# Fri3d_2026_DJ_00.net
KiCad netlist of a schematic drawn in Altium Designer
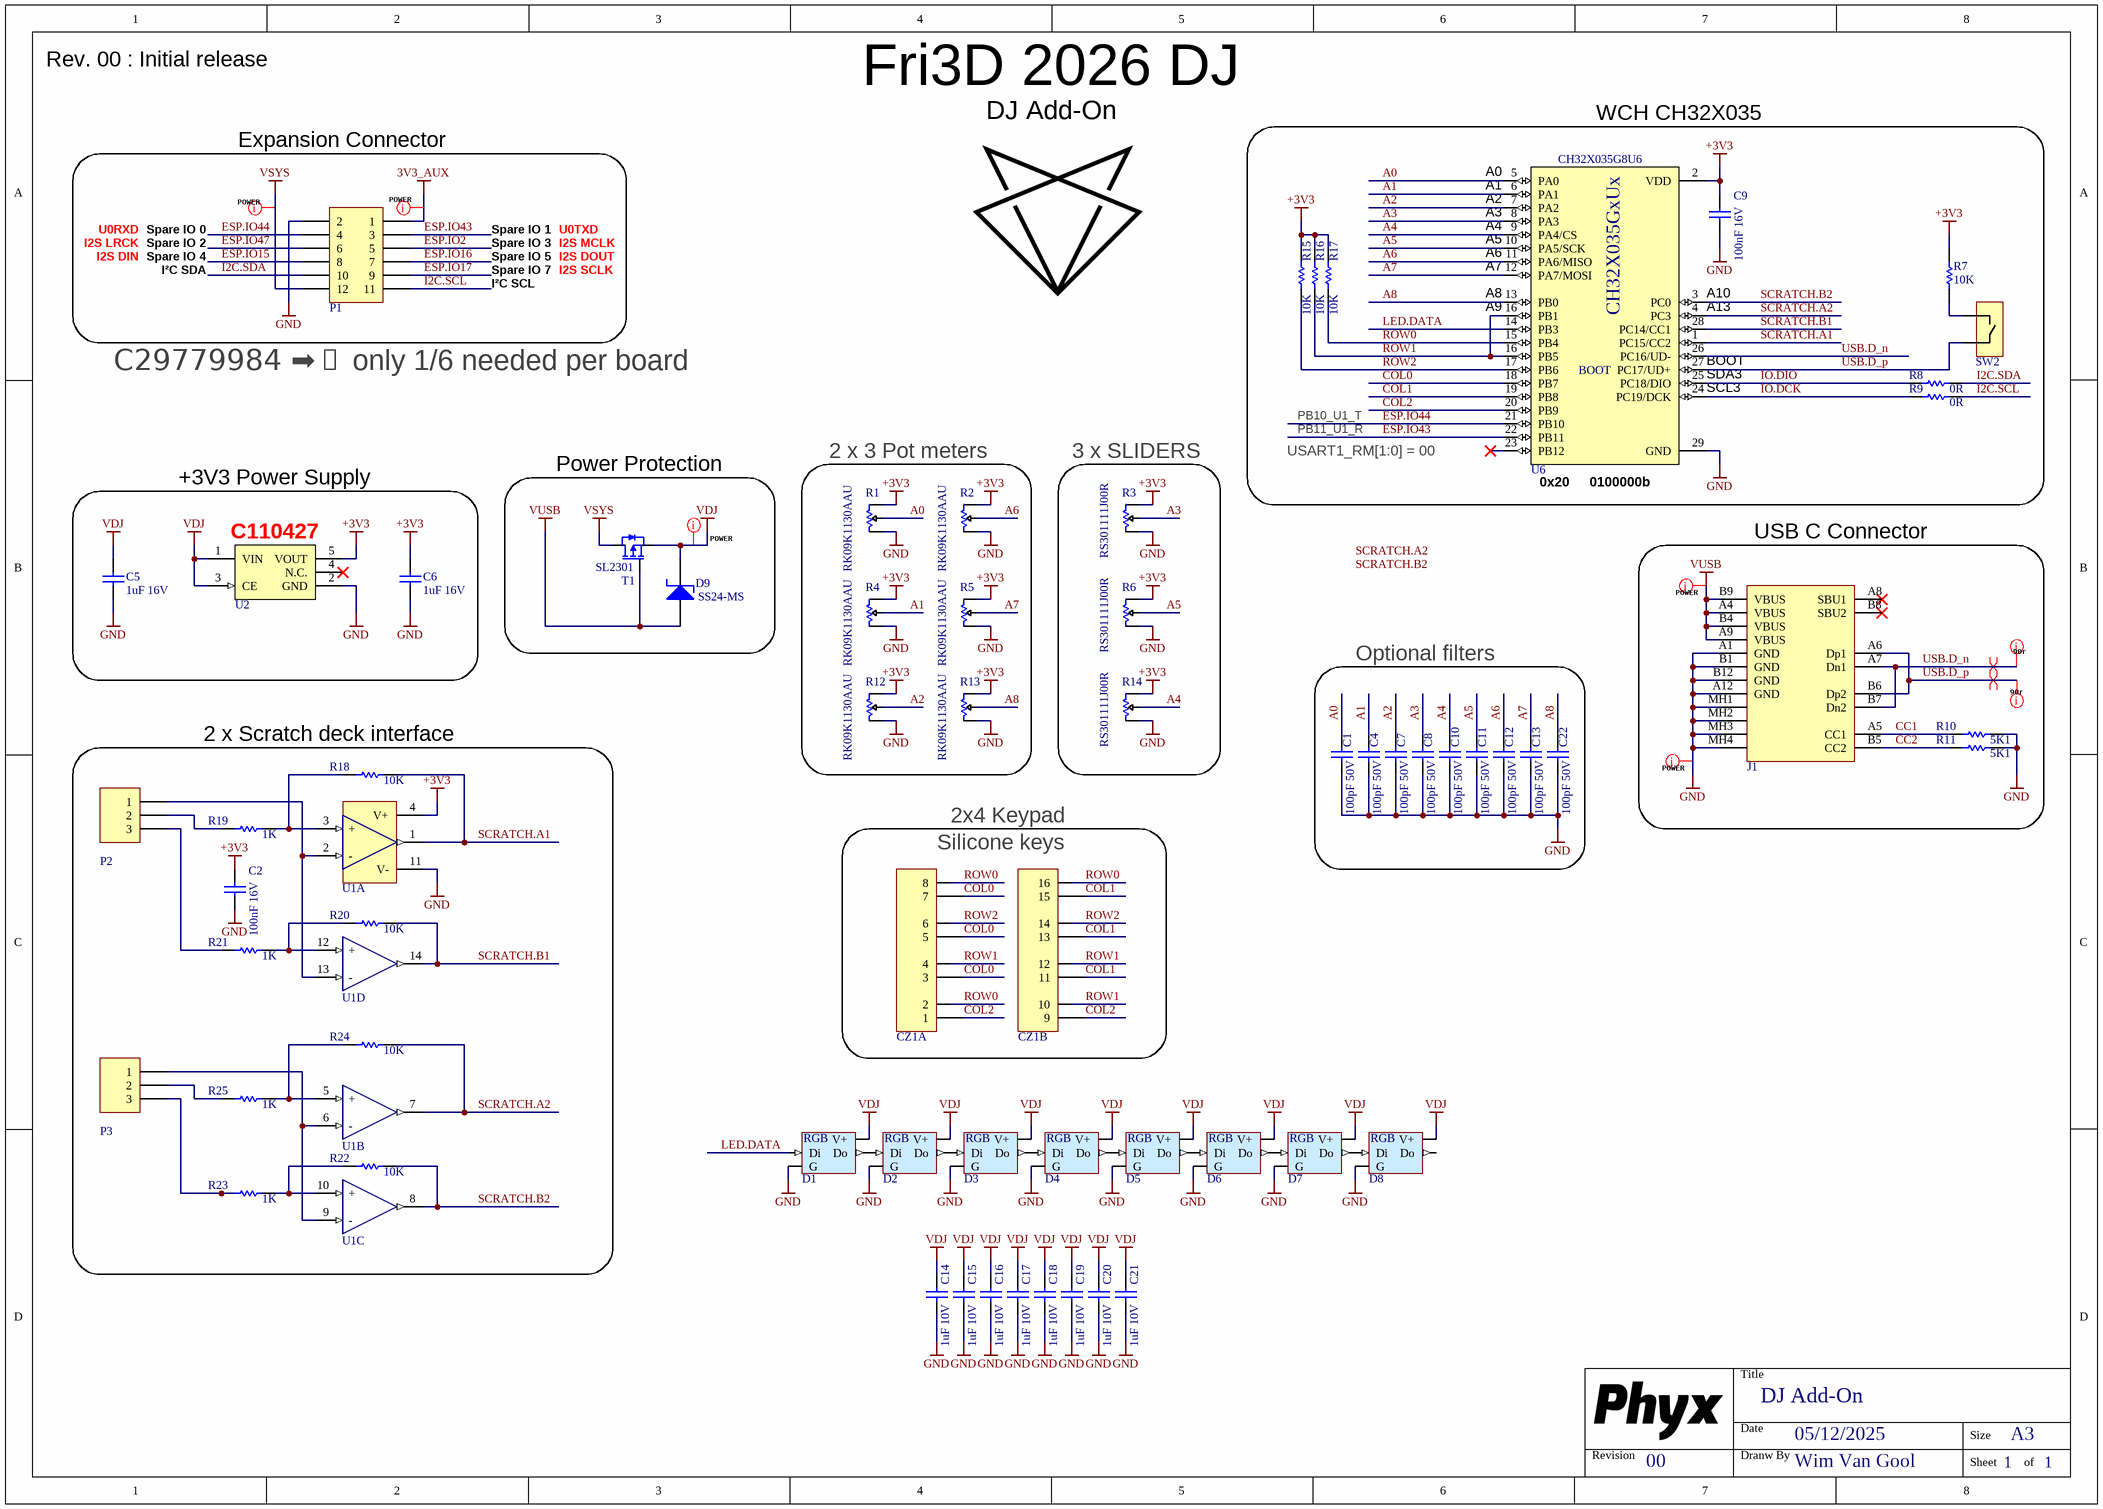
[diagram p0: Fri3d_2026_DJ_00.SchDoc]

(export (version "E")
  (design (tool "Eeschema 10.0.6"))
  (components
    (comp (ref "C1")
      (value "100pF 50V")
      (footprint "C0603_N")
      (description "Capacitor Ceramic")
      (libsource (lib "Phyx_Components") (part "CAP_CERAMIC"))
    )
    (comp (ref "C2")
      (value "100nF 16V")
      (footprint "C0603_N")
      (description "Capacitor Ceramic")
      (libsource (lib "Phyx_Components") (part "CAP_CERAMIC"))
    )
    (comp (ref "C4")
      (value "100pF 50V")
      (footprint "C0603_N")
      (description "Capacitor Ceramic")
      (libsource (lib "Phyx_Components") (part "CAP_CERAMIC"))
    )
    (comp (ref "C5")
      (value "1uF 16V")
      (footprint "C0603_N")
      (description "Capacitor Ceramic")
      (libsource (lib "Phyx_Components") (part "CAP_CERAMIC"))
    )
    (comp (ref "C6")
      (value "1uF 16V")
      (footprint "C0603_N")
      (description "Capacitor Ceramic")
      (libsource (lib "Phyx_Components") (part "CAP_CERAMIC"))
    )
    (comp (ref "C7")
      (value "100pF 50V")
      (footprint "C0603_N")
      (description "Capacitor Ceramic")
      (libsource (lib "Phyx_Components") (part "CAP_CERAMIC"))
    )
    (comp (ref "C8")
      (value "100pF 50V")
      (footprint "C0603_N")
      (description "Capacitor Ceramic")
      (libsource (lib "Phyx_Components") (part "CAP_CERAMIC"))
    )
    (comp (ref "C9")
      (value "100nF 16V")
      (footprint "C0603_N")
      (description "Capacitor Ceramic")
      (libsource (lib "Phyx_Components") (part "CAP_CERAMIC"))
    )
    (comp (ref "C10")
      (value "100pF 50V")
      (footprint "C0603_N")
      (description "Capacitor Ceramic")
      (libsource (lib "Phyx_Components") (part "CAP_CERAMIC"))
    )
    (comp (ref "C11")
      (value "100pF 50V")
      (footprint "C0603_N")
      (description "Capacitor Ceramic")
      (libsource (lib "Phyx_Components") (part "CAP_CERAMIC"))
    )
    (comp (ref "C12")
      (value "100pF 50V")
      (footprint "C0603_N")
      (description "Capacitor Ceramic")
      (libsource (lib "Phyx_Components") (part "CAP_CERAMIC"))
    )
    (comp (ref "C13")
      (value "100pF 50V")
      (footprint "C0603_N")
      (description "Capacitor Ceramic")
      (libsource (lib "Phyx_Components") (part "CAP_CERAMIC"))
    )
    (comp (ref "C14")
      (value "1uF 10V")
      (footprint "C0402")
      (description "Capacitor Ceramic")
      (libsource (lib "Phyx_Components") (part "CAP_CERAMIC"))
    )
    (comp (ref "C15")
      (value "1uF 10V")
      (footprint "C0402")
      (description "Capacitor Ceramic")
      (libsource (lib "Phyx_Components") (part "CAP_CERAMIC"))
    )
    (comp (ref "C16")
      (value "1uF 10V")
      (footprint "C0402")
      (description "Capacitor Ceramic")
      (libsource (lib "Phyx_Components") (part "CAP_CERAMIC"))
    )
    (comp (ref "C17")
      (value "1uF 10V")
      (footprint "C0402")
      (description "Capacitor Ceramic")
      (libsource (lib "Phyx_Components") (part "CAP_CERAMIC"))
    )
    (comp (ref "C18")
      (value "1uF 10V")
      (footprint "C0402")
      (description "Capacitor Ceramic")
      (libsource (lib "Phyx_Components") (part "CAP_CERAMIC"))
    )
    (comp (ref "C19")
      (value "1uF 10V")
      (footprint "C0402")
      (description "Capacitor Ceramic")
      (libsource (lib "Phyx_Components") (part "CAP_CERAMIC"))
    )
    (comp (ref "C20")
      (value "1uF 10V")
      (footprint "C0402")
      (description "Capacitor Ceramic")
      (libsource (lib "Phyx_Components") (part "CAP_CERAMIC"))
    )
    (comp (ref "C21")
      (value "1uF 10V")
      (footprint "C0402")
      (description "Capacitor Ceramic")
      (libsource (lib "Phyx_Components") (part "CAP_CERAMIC"))
    )
    (comp (ref "C22")
      (value "100pF 50V")
      (footprint "C0603_N")
      (description "Capacitor Ceramic")
      (libsource (lib "Phyx_Components") (part "CAP_CERAMIC"))
    )
    (comp (ref "CZ1")
      (value "Campzone 2020 2x4 silicone keypad")
      (footprint "CZ20_2x4")
      (libsource (lib "Phyx_Components") (part "CZ20_2x4"))
    )
    (comp (ref "D1")
      (value "WS2812 based digital RGB LED 5050 White package reduced current")
      (footprint "LED_5050_WS2812B_WHITE")
      (description "=Description")
      (libsource (lib "Phyx_Components") (part "LED_RGB_WS2812B_5050"))
    )
    (comp (ref "D2")
      (value "WS2812 based digital RGB LED 5050 White package reduced current")
      (footprint "LED_5050_WS2812B_WHITE")
      (description "=Description")
      (libsource (lib "Phyx_Components") (part "LED_RGB_WS2812B_5050"))
    )
    (comp (ref "D3")
      (value "WS2812 based digital RGB LED 5050 White package reduced current")
      (footprint "LED_5050_WS2812B_WHITE")
      (description "=Description")
      (libsource (lib "Phyx_Components") (part "LED_RGB_WS2812B_5050"))
    )
    (comp (ref "D4")
      (value "WS2812 based digital RGB LED 5050 White package reduced current")
      (footprint "LED_5050_WS2812B_WHITE")
      (description "=Description")
      (libsource (lib "Phyx_Components") (part "LED_RGB_WS2812B_5050"))
    )
    (comp (ref "D5")
      (value "WS2812 based digital RGB LED 5050 White package reduced current")
      (footprint "LED_5050_WS2812B_WHITE")
      (description "=Description")
      (libsource (lib "Phyx_Components") (part "LED_RGB_WS2812B_5050"))
    )
    (comp (ref "D6")
      (value "WS2812 based digital RGB LED 5050 White package reduced current")
      (footprint "LED_5050_WS2812B_WHITE")
      (description "=Description")
      (libsource (lib "Phyx_Components") (part "LED_RGB_WS2812B_5050"))
    )
    (comp (ref "D7")
      (value "WS2812 based digital RGB LED 5050 White package reduced current")
      (footprint "LED_5050_WS2812B_WHITE")
      (description "=Description")
      (libsource (lib "Phyx_Components") (part "LED_RGB_WS2812B_5050"))
    )
    (comp (ref "D8")
      (value "WS2812 based digital RGB LED 5050 White package reduced current")
      (footprint "LED_5050_WS2812B_WHITE")
      (description "=Description")
      (libsource (lib "Phyx_Components") (part "LED_RGB_WS2812B_5050"))
    )
    (comp (ref "D9")
      (value "SS24-MS")
      (footprint "DO-214AC_AC")
      (description "=Description")
      (fields (field (name "Comment") "40V 2A 550mV@2A DO-214 Schottky"))
      (libsource (lib "Phyx_Components") (part "Schottky_AC"))
    )
    (comp (ref "J1")
      (value "USB 2.0 C Reversible Receptacle Horizontal full SMD")
      (footprint "XUNPU-TYPEC-304S-ACP16")
      (libsource (lib "Phyx_Components") (part "USB_C_16_4"))
    )
    (comp (ref "P1")
      (value "Header 6X2")
      (footprint "HDR2X6")
      (libsource (lib "Phyx_Components") (part "Header 6X2"))
    )
    (comp (ref "P2")
      (value "Header 3")
      (footprint "HDR1X3")
      (description "Pin Header 2.54mm 3way")
      (libsource (lib "Phyx_Components") (part "Header 3"))
    )
    (comp (ref "P3")
      (value "Header 3")
      (footprint "HDR1X3")
      (description "Pin Header 2.54mm 3way")
      (libsource (lib "Phyx_Components") (part "Header 3"))
    )
    (comp (ref "R1")
      (value "RK09K1130AAU")
      (footprint "ALPS_RK09K1130AAU")
      (fields (field (name "Comment") "10kΩ Rotary Potentiometers"))
      (libsource (lib "Phyx_Components") (part "RES_VAR"))
    )
    (comp (ref "R2")
      (value "RK09K1130AAU")
      (footprint "ALPS_RK09K1130AAU")
      (fields (field (name "Comment") "10kΩ Rotary Potentiometers"))
      (libsource (lib "Phyx_Components") (part "RES_VAR"))
    )
    (comp (ref "R3")
      (value "RS301111J00R")
      (footprint "ALPS_RS301111J00R")
      (fields (field (name "Comment") "50kΩ Slide Potentiometers"))
      (libsource (lib "Phyx_Components") (part "RES_VAR"))
    )
    (comp (ref "R4")
      (value "RK09K1130AAU")
      (footprint "ALPS_RK09K1130AAU")
      (fields (field (name "Comment") "10kΩ Rotary Potentiometers"))
      (libsource (lib "Phyx_Components") (part "RES_VAR"))
    )
    (comp (ref "R5")
      (value "RK09K1130AAU")
      (footprint "ALPS_RK09K1130AAU")
      (fields (field (name "Comment") "10kΩ Rotary Potentiometers"))
      (libsource (lib "Phyx_Components") (part "RES_VAR"))
    )
    (comp (ref "R6")
      (value "RS301111J00R")
      (footprint "ALPS_RS301111J00R")
      (fields (field (name "Comment") "50kΩ Slide Potentiometers"))
      (libsource (lib "Phyx_Components") (part "RES_VAR"))
    )
    (comp (ref "R7")
      (value "10K")
      (footprint "R0603_N")
      (libsource (lib "Phyx_Components") (part "RESISTOR"))
    )
    (comp (ref "R8") (value "0R") (footprint "R0603_N") (libsource (lib "Phyx_Components") (part "RESISTOR")))
    (comp (ref "R9") (value "0R") (footprint "R0603_N") (libsource (lib "Phyx_Components") (part "RESISTOR")))
    (comp (ref "R10")
      (value "5K1")
      (footprint "R0603_N")
      (libsource (lib "Phyx_Components") (part "RESISTOR"))
    )
    (comp (ref "R11")
      (value "5K1")
      (footprint "R0603_N")
      (libsource (lib "Phyx_Components") (part "RESISTOR"))
    )
    (comp (ref "R12")
      (value "RK09K1130AAU")
      (footprint "ALPS_RK09K1130AAU")
      (fields (field (name "Comment") "10kΩ Rotary Potentiometers"))
      (libsource (lib "Phyx_Components") (part "RES_VAR"))
    )
    (comp (ref "R13")
      (value "RK09K1130AAU")
      (footprint "ALPS_RK09K1130AAU")
      (fields (field (name "Comment") "10kΩ Rotary Potentiometers"))
      (libsource (lib "Phyx_Components") (part "RES_VAR"))
    )
    (comp (ref "R14")
      (value "RS301111J00R")
      (footprint "ALPS_RS301111J00R")
      (fields (field (name "Comment") "50kΩ Slide Potentiometers"))
      (libsource (lib "Phyx_Components") (part "RES_VAR"))
    )
    (comp (ref "R15")
      (value "10K")
      (footprint "R0603_N")
      (libsource (lib "Phyx_Components") (part "RESISTOR"))
    )
    (comp (ref "R16")
      (value "10K")
      (footprint "R0603_N")
      (libsource (lib "Phyx_Components") (part "RESISTOR"))
    )
    (comp (ref "R17")
      (value "10K")
      (footprint "R0603_N")
      (libsource (lib "Phyx_Components") (part "RESISTOR"))
    )
    (comp (ref "R18")
      (value "10K")
      (footprint "R0603_N")
      (libsource (lib "Phyx_Components") (part "RESISTOR"))
    )
    (comp (ref "R19")
      (value "1K")
      (footprint "R0603_N")
      (libsource (lib "Phyx_Components") (part "RESISTOR"))
    )
    (comp (ref "R20")
      (value "10K")
      (footprint "R0603_N")
      (libsource (lib "Phyx_Components") (part "RESISTOR"))
    )
    (comp (ref "R21")
      (value "1K")
      (footprint "R0603_N")
      (libsource (lib "Phyx_Components") (part "RESISTOR"))
    )
    (comp (ref "R22")
      (value "10K")
      (footprint "R0603_N")
      (libsource (lib "Phyx_Components") (part "RESISTOR"))
    )
    (comp (ref "R23")
      (value "1K")
      (footprint "R0603_N")
      (libsource (lib "Phyx_Components") (part "RESISTOR"))
    )
    (comp (ref "R24")
      (value "10K")
      (footprint "R0603_N")
      (libsource (lib "Phyx_Components") (part "RESISTOR"))
    )
    (comp (ref "R25")
      (value "1K")
      (footprint "R0603_N")
      (libsource (lib "Phyx_Components") (part "RESISTOR"))
    )
    (comp (ref "SW2")
      (value "4.5x4.5mm tact SMD H3,8mm")
      (footprint "WE_430181038816")
      (libsource (lib "Phyx_Components") (part "SW_TACT"))
    )
    (comp (ref "T1")
      (value "SL2301")
      (footprint "SOT23-3")
      (description "=Description")
      (fields (field (name "Comment") "-2.3A -20V P-Ch MOSFET Vgs -1V"))
      (libsource (lib "Phyx_Components") (part "P_MOSFET_GSD"))
    )
    (comp (ref "U1")
      (value "Quad, 30-V, 1-MHz operational amplifier")
      (footprint "SOIC_N_14")
      (description "=Description")
      (libsource (lib "Phyx_Components") (part "OPA4134"))
    )
    (comp (ref "U2")
      (value "3V3 LDO 300mA 150mV")
      (footprint "SOT23-5")
      (description "=Designator")
      (libsource (lib "Phyx_Components") (part "XC6210_SOT"))
    )
    (comp (ref "U6")
      (value "CH32X035G8U6")
      (footprint "QFN_28_4.0x4.0_P0.4")
      (fields
        (field (name "Comment") "WCH CH32X035G8U6 QFN28 RISC-V 32-bit MCU, 62KB Flash, 10KB RAM, USB PD")
      )
      (libsource (lib "Phyx_Components") (part "WCH_CH32X035GxUx"))
    )
  )
  (nets
    (net (code "1") (name "+3V3") (class "Default")
      (node (ref "C2") (pin "1") (pinfunction "1_1") (pintype "passive"))
      (node (ref "C6") (pin "1") (pinfunction "1_1") (pintype "passive"))
      (node (ref "C9") (pin "1") (pinfunction "1_1") (pintype "passive"))
      (node (ref "R1") (pin "1") (pinfunction "1_1") (pintype "passive"))
      (node (ref "R12") (pin "1") (pinfunction "1_1") (pintype "passive"))
      (node (ref "R13") (pin "1") (pinfunction "1_1") (pintype "passive"))
      (node (ref "R14") (pin "1") (pinfunction "1_1") (pintype "passive"))
      (node (ref "R15") (pin "1") (pinfunction "1_1") (pintype "passive"))
      (node (ref "R16") (pin "1") (pinfunction "1_1") (pintype "passive"))
      (node (ref "R17") (pin "1") (pinfunction "1_1") (pintype "passive"))
      (node (ref "R2") (pin "1") (pinfunction "1_1") (pintype "passive"))
      (node (ref "R3") (pin "1") (pinfunction "1_1") (pintype "passive"))
      (node (ref "R4") (pin "1") (pinfunction "1_1") (pintype "passive"))
      (node (ref "R5") (pin "1") (pinfunction "1_1") (pintype "passive"))
      (node (ref "R6") (pin "1") (pinfunction "1_1") (pintype "passive"))
      (node (ref "R7") (pin "1") (pinfunction "1_1") (pintype "passive"))
      (node (ref "U1") (pin "4") (pinfunction "V+_4") (pintype "power_in"))
      (node (ref "U2") (pin "5") (pinfunction "VOUT_5") (pintype "power_in"))
      (node (ref "U6") (pin "2") (pinfunction "VDD_2") (pintype "power_in"))
    )
    (net (code "2") (name "/A0") (class "Default")
      (node (ref "C1") (pin "1") (pinfunction "1_1") (pintype "passive"))
      (node (ref "R1") (pin "2") (pinfunction "2_2") (pintype "passive"))
      (node (ref "U6") (pin "5") (pinfunction "PA0_5") (pintype "bidirectional"))
    )
    (net (code "3") (name "/A1") (class "Default")
      (node (ref "C4") (pin "1") (pinfunction "1_1") (pintype "passive"))
      (node (ref "R4") (pin "2") (pinfunction "2_2") (pintype "passive"))
      (node (ref "U6") (pin "6") (pinfunction "PA1_6") (pintype "bidirectional"))
    )
    (net (code "4") (name "/A2") (class "Default")
      (node (ref "C7") (pin "1") (pinfunction "1_1") (pintype "passive"))
      (node (ref "R12") (pin "2") (pinfunction "2_2") (pintype "passive"))
      (node (ref "U6") (pin "7") (pinfunction "PA2_7") (pintype "bidirectional"))
    )
    (net (code "5") (name "/A3") (class "Default")
      (node (ref "C8") (pin "1") (pinfunction "1_1") (pintype "passive"))
      (node (ref "R3") (pin "2") (pinfunction "2_2") (pintype "passive"))
      (node (ref "U6") (pin "8") (pinfunction "PA3_8") (pintype "bidirectional"))
    )
    (net (code "6") (name "/A4") (class "Default")
      (node (ref "C10") (pin "1") (pinfunction "1_1") (pintype "passive"))
      (node (ref "R14") (pin "2") (pinfunction "2_2") (pintype "passive"))
      (node (ref "U6") (pin "9") (pinfunction "PA4/CS_9") (pintype "bidirectional"))
    )
    (net (code "7") (name "/A5") (class "Default")
      (node (ref "C11") (pin "1") (pinfunction "1_1") (pintype "passive"))
      (node (ref "R6") (pin "2") (pinfunction "2_2") (pintype "passive"))
      (node (ref "U6") (pin "10") (pinfunction "PA5/SCK_10") (pintype "bidirectional"))
    )
    (net (code "8") (name "/A6") (class "Default")
      (node (ref "C12") (pin "1") (pinfunction "1_1") (pintype "passive"))
      (node (ref "R2") (pin "2") (pinfunction "2_2") (pintype "passive"))
      (node (ref "U6") (pin "11") (pinfunction "PA6/MISO_11") (pintype "bidirectional"))
    )
    (net (code "9") (name "/A7") (class "Default")
      (node (ref "C13") (pin "1") (pinfunction "1_1") (pintype "passive"))
      (node (ref "R5") (pin "2") (pinfunction "2_2") (pintype "passive"))
      (node (ref "U6") (pin "12") (pinfunction "PA7/MOSI_12") (pintype "bidirectional"))
    )
    (net (code "10") (name "/A8") (class "Default")
      (node (ref "C22") (pin "1") (pinfunction "1_1") (pintype "passive"))
      (node (ref "R13") (pin "2") (pinfunction "2_2") (pintype "passive"))
      (node (ref "U6") (pin "13") (pinfunction "PB0_13") (pintype "bidirectional"))
    )
    (net (code "11") (name "/CC1") (class "Default")
      (node (ref "J1") (pin "A5") (pinfunction "CC1_A5") (pintype "passive"))
      (node (ref "R10") (pin "1") (pinfunction "1_1") (pintype "passive"))
    )
    (net (code "12") (name "/CC2") (class "Default")
      (node (ref "J1") (pin "B5") (pinfunction "CC2_B5") (pintype "passive"))
      (node (ref "R11") (pin "1") (pinfunction "1_1") (pintype "passive"))
    )
    (net (code "13") (name "/COL0") (class "Default")
      (node (ref "CZ1") (pin "3") (pinfunction "3_3") (pintype "passive"))
      (node (ref "CZ1") (pin "5") (pinfunction "5_5") (pintype "passive"))
      (node (ref "CZ1") (pin "7") (pinfunction "7_7") (pintype "passive"))
      (node (ref "U6") (pin "18") (pinfunction "PB7_18") (pintype "bidirectional"))
    )
    (net (code "14") (name "/COL1") (class "Default")
      (node (ref "CZ1") (pin "11") (pinfunction "11_11") (pintype "passive"))
      (node (ref "CZ1") (pin "13") (pinfunction "13_13") (pintype "passive"))
      (node (ref "CZ1") (pin "15") (pinfunction "15_15") (pintype "passive"))
      (node (ref "U6") (pin "19") (pinfunction "PB8_19") (pintype "bidirectional"))
    )
    (net (code "15") (name "/COL2") (class "Default")
      (node (ref "CZ1") (pin "1") (pinfunction "1_1") (pintype "passive"))
      (node (ref "CZ1") (pin "9") (pinfunction "9_9") (pintype "passive"))
      (node (ref "U6") (pin "20") (pinfunction "PB9_20") (pintype "bidirectional"))
    )
    (net (code "16") (name "/ESP.IO2") (class "Default")
      (node (ref "P1") (pin "5") (pinfunction "5_5") (pintype "passive"))
    )
    (net (code "17") (name "/ESP.IO15") (class "Default")
      (node (ref "P1") (pin "8") (pinfunction "8_8") (pintype "passive"))
    )
    (net (code "18") (name "/ESP.IO16") (class "Default")
      (node (ref "P1") (pin "7") (pinfunction "7_7") (pintype "passive"))
    )
    (net (code "19") (name "/ESP.IO17") (class "Default")
      (node (ref "P1") (pin "9") (pinfunction "9_9") (pintype "passive"))
    )
    (net (code "20") (name "/ESP.IO43") (class "Default")
      (node (ref "P1") (pin "3") (pinfunction "3_3") (pintype "passive"))
      (node (ref "U6") (pin "22") (pinfunction "PB11_22") (pintype "bidirectional"))
    )
    (net (code "21") (name "/ESP.IO44") (class "Default")
      (node (ref "P1") (pin "4") (pinfunction "4_4") (pintype "passive"))
      (node (ref "U6") (pin "21") (pinfunction "PB10_21") (pintype "bidirectional"))
    )
    (net (code "22") (name "/ESP.IO47") (class "Default")
      (node (ref "P1") (pin "6") (pinfunction "6_6") (pintype "passive"))
    )
    (net (code "23") (name "/I2C.SCL") (class "Default")
      (node (ref "P1") (pin "11") (pinfunction "11_11") (pintype "passive"))
      (node (ref "R9") (pin "2") (pinfunction "2_2") (pintype "passive"))
    )
    (net (code "24") (name "/I2C.SDA") (class "Default")
      (node (ref "P1") (pin "10") (pinfunction "10_10") (pintype "passive"))
      (node (ref "R8") (pin "2") (pinfunction "2_2") (pintype "passive"))
    )
    (net (code "25") (name "/IO.DCK") (class "Default")
      (node (ref "R9") (pin "1") (pinfunction "1_1") (pintype "passive"))
      (node (ref "U6") (pin "24") (pinfunction "PC19/DCK_24") (pintype "bidirectional"))
    )
    (net (code "26") (name "/IO.DIO") (class "Default")
      (node (ref "R8") (pin "1") (pinfunction "1_1") (pintype "passive"))
      (node (ref "U6") (pin "25") (pinfunction "PC18/DIO_25") (pintype "bidirectional"))
    )
    (net (code "27") (name "/LED.DATA") (class "Default")
      (node (ref "D1") (pin "4") (pinfunction "Di_4") (pintype "input"))
      (node (ref "U6") (pin "14") (pinfunction "PB3_14") (pintype "bidirectional"))
    )
    (net (code "28") (name "/ROW0") (class "Default")
      (node (ref "CZ1") (pin "16") (pinfunction "16_16") (pintype "passive"))
      (node (ref "CZ1") (pin "2") (pinfunction "2_2") (pintype "passive"))
      (node (ref "CZ1") (pin "8") (pinfunction "8_8") (pintype "passive"))
      (node (ref "R17") (pin "2") (pinfunction "2_2") (pintype "passive"))
      (node (ref "U6") (pin "15") (pinfunction "PB4_15") (pintype "bidirectional"))
    )
    (net (code "29") (name "/ROW1") (class "Default")
      (node (ref "CZ1") (pin "10") (pinfunction "10_10") (pintype "passive"))
      (node (ref "CZ1") (pin "12") (pinfunction "12_12") (pintype "passive"))
      (node (ref "CZ1") (pin "4") (pinfunction "4_4") (pintype "passive"))
      (node (ref "R16") (pin "2") (pinfunction "2_2") (pintype "passive"))
      (node (ref "U6") (pin "16") (pinfunction "PB1_16") (pintype "bidirectional"))
    )
    (net (code "30") (name "/ROW2") (class "Default")
      (node (ref "CZ1") (pin "14") (pinfunction "14_14") (pintype "passive"))
      (node (ref "CZ1") (pin "6") (pinfunction "6_6") (pintype "passive"))
      (node (ref "R15") (pin "2") (pinfunction "2_2") (pintype "passive"))
      (node (ref "U6") (pin "17") (pinfunction "PB6_17") (pintype "bidirectional"))
    )
    (net (code "31") (name "/SCRATCH.A1") (class "Default")
      (node (ref "R18") (pin "1") (pinfunction "1_1") (pintype "passive"))
      (node (ref "U1") (pin "1") (pinfunction "OUT_1") (pintype "output"))
      (node (ref "U6") (pin "1") (pinfunction "PC15/CC2_1") (pintype "bidirectional"))
    )
    (net (code "32") (name "/SCRATCH.A2") (class "Default")
      (node (ref "R24") (pin "1") (pinfunction "1_1") (pintype "passive"))
      (node (ref "U1") (pin "7") (pinfunction "OUT_7") (pintype "output"))
      (node (ref "U6") (pin "4") (pinfunction "PC3_4") (pintype "bidirectional"))
    )
    (net (code "33") (name "/SCRATCH.B1") (class "Default")
      (node (ref "R20") (pin "1") (pinfunction "1_1") (pintype "passive"))
      (node (ref "U1") (pin "14") (pinfunction "OUT_14") (pintype "output"))
      (node (ref "U6") (pin "28") (pinfunction "PC14/CC1_28") (pintype "bidirectional"))
    )
    (net (code "34") (name "/SCRATCH.B2") (class "Default")
      (node (ref "R22") (pin "1") (pinfunction "1_1") (pintype "passive"))
      (node (ref "U1") (pin "8") (pinfunction "OUT_8") (pintype "output"))
      (node (ref "U6") (pin "3") (pinfunction "PC0_3") (pintype "bidirectional"))
    )
    (net (code "35") (name "/USB.D_n") (class "Default")
      (node (ref "J1") (pin "A7") (pinfunction "Dn1_A7") (pintype "passive"))
      (node (ref "J1") (pin "B7") (pinfunction "Dn2_B7") (pintype "passive"))
      (node (ref "U6") (pin "26") (pinfunction "PC16/UD-_26") (pintype "bidirectional"))
    )
    (net (code "36") (name "/USB.D_p") (class "Default")
      (node (ref "J1") (pin "A6") (pinfunction "Dp1_A6") (pintype "passive"))
      (node (ref "J1") (pin "B6") (pinfunction "Dp2_B6") (pintype "passive"))
      (node (ref "SW2") (pin "2") (pinfunction "2_2") (pintype "passive"))
      (node (ref "U6") (pin "27") (pinfunction "PC17/UD+_27") (pintype "bidirectional"))
    )
    (net (code "37") (name "3V3_AUX") (class "Default")
      (node (ref "P1") (pin "1") (pinfunction "1_1") (pintype "passive"))
    )
    (net (code "38") (name "GND") (class "Default")
      (node (ref "C1") (pin "2") (pinfunction "2_2") (pintype "passive"))
      (node (ref "C10") (pin "2") (pinfunction "2_2") (pintype "passive"))
      (node (ref "C11") (pin "2") (pinfunction "2_2") (pintype "passive"))
      (node (ref "C12") (pin "2") (pinfunction "2_2") (pintype "passive"))
      (node (ref "C13") (pin "2") (pinfunction "2_2") (pintype "passive"))
      (node (ref "C14") (pin "2") (pinfunction "2_2") (pintype "passive"))
      (node (ref "C15") (pin "2") (pinfunction "2_2") (pintype "passive"))
      (node (ref "C16") (pin "2") (pinfunction "2_2") (pintype "passive"))
      (node (ref "C17") (pin "2") (pinfunction "2_2") (pintype "passive"))
      (node (ref "C18") (pin "2") (pinfunction "2_2") (pintype "passive"))
      (node (ref "C19") (pin "2") (pinfunction "2_2") (pintype "passive"))
      (node (ref "C2") (pin "2") (pinfunction "2_2") (pintype "passive"))
      (node (ref "C20") (pin "2") (pinfunction "2_2") (pintype "passive"))
      (node (ref "C21") (pin "2") (pinfunction "2_2") (pintype "passive"))
      (node (ref "C22") (pin "2") (pinfunction "2_2") (pintype "passive"))
      (node (ref "C4") (pin "2") (pinfunction "2_2") (pintype "passive"))
      (node (ref "C5") (pin "2") (pinfunction "2_2") (pintype "passive"))
      (node (ref "C6") (pin "2") (pinfunction "2_2") (pintype "passive"))
      (node (ref "C7") (pin "2") (pinfunction "2_2") (pintype "passive"))
      (node (ref "C8") (pin "2") (pinfunction "2_2") (pintype "passive"))
      (node (ref "C9") (pin "2") (pinfunction "2_2") (pintype "passive"))
      (node (ref "D1") (pin "3") (pinfunction "G_3") (pintype "power_in"))
      (node (ref "D2") (pin "3") (pinfunction "G_3") (pintype "power_in"))
      (node (ref "D3") (pin "3") (pinfunction "G_3") (pintype "power_in"))
      (node (ref "D4") (pin "3") (pinfunction "G_3") (pintype "power_in"))
      (node (ref "D5") (pin "3") (pinfunction "G_3") (pintype "power_in"))
      (node (ref "D6") (pin "3") (pinfunction "G_3") (pintype "power_in"))
      (node (ref "D7") (pin "3") (pinfunction "G_3") (pintype "power_in"))
      (node (ref "D8") (pin "3") (pinfunction "G_3") (pintype "power_in"))
      (node (ref "J1") (pin "A1") (pinfunction "GND_A1") (pintype "passive"))
      (node (ref "J1") (pin "A12") (pinfunction "GND_A12") (pintype "passive"))
      (node (ref "J1") (pin "B1") (pinfunction "GND_B1") (pintype "passive"))
      (node (ref "J1") (pin "B12") (pinfunction "GND_B12") (pintype "passive"))
      (node (ref "J1") (pin "MH1") (pinfunction "Tab_MH1") (pintype "passive"))
      (node (ref "J1") (pin "MH2") (pinfunction "Tab_MH2") (pintype "passive"))
      (node (ref "J1") (pin "MH3") (pinfunction "Tab_MH3") (pintype "passive"))
      (node (ref "J1") (pin "MH4") (pinfunction "Tab_MH4") (pintype "passive"))
      (node (ref "P1") (pin "2") (pinfunction "2_2") (pintype "passive"))
      (node (ref "R1") (pin "3") (pinfunction "3_3") (pintype "passive"))
      (node (ref "R10") (pin "2") (pinfunction "2_2") (pintype "passive"))
      (node (ref "R11") (pin "2") (pinfunction "2_2") (pintype "passive"))
      (node (ref "R12") (pin "3") (pinfunction "3_3") (pintype "passive"))
      (node (ref "R13") (pin "3") (pinfunction "3_3") (pintype "passive"))
      (node (ref "R14") (pin "3") (pinfunction "3_3") (pintype "passive"))
      (node (ref "R2") (pin "3") (pinfunction "3_3") (pintype "passive"))
      (node (ref "R3") (pin "3") (pinfunction "3_3") (pintype "passive"))
      (node (ref "R4") (pin "3") (pinfunction "3_3") (pintype "passive"))
      (node (ref "R5") (pin "3") (pinfunction "3_3") (pintype "passive"))
      (node (ref "R6") (pin "3") (pinfunction "3_3") (pintype "passive"))
      (node (ref "U1") (pin "11") (pinfunction "V-_11") (pintype "power_in"))
      (node (ref "U2") (pin "2") (pinfunction "GND_2") (pintype "power_in"))
      (node (ref "U6") (pin "29") (pinfunction "GND_29") (pintype "power_in"))
    )
    (net (code "39") (name "Net-(D1-Do)") (class "Default")
      (node (ref "D1") (pin "2") (pinfunction "Do_2") (pintype "output"))
      (node (ref "D2") (pin "4") (pinfunction "Di_4") (pintype "input"))
    )
    (net (code "40") (name "Net-(D2-Do)") (class "Default")
      (node (ref "D2") (pin "2") (pinfunction "Do_2") (pintype "output"))
      (node (ref "D3") (pin "4") (pinfunction "Di_4") (pintype "input"))
    )
    (net (code "41") (name "Net-(D3-Do)") (class "Default")
      (node (ref "D3") (pin "2") (pinfunction "Do_2") (pintype "output"))
      (node (ref "D4") (pin "4") (pinfunction "Di_4") (pintype "input"))
    )
    (net (code "42") (name "Net-(D4-Do)") (class "Default")
      (node (ref "D4") (pin "2") (pinfunction "Do_2") (pintype "output"))
      (node (ref "D5") (pin "4") (pinfunction "Di_4") (pintype "input"))
    )
    (net (code "43") (name "Net-(D5-Do)") (class "Default")
      (node (ref "D5") (pin "2") (pinfunction "Do_2") (pintype "output"))
      (node (ref "D6") (pin "4") (pinfunction "Di_4") (pintype "input"))
    )
    (net (code "44") (name "Net-(D6-Do)") (class "Default")
      (node (ref "D6") (pin "2") (pinfunction "Do_2") (pintype "output"))
      (node (ref "D7") (pin "4") (pinfunction "Di_4") (pintype "input"))
    )
    (net (code "45") (name "Net-(D7-Do)") (class "Default")
      (node (ref "D7") (pin "2") (pinfunction "Do_2") (pintype "output"))
      (node (ref "D8") (pin "4") (pinfunction "Di_4") (pintype "input"))
    )
    (net (code "46") (name "Net-(P2-Pad2)") (class "Default")
      (node (ref "P2") (pin "2") (pinfunction "2_2") (pintype "passive"))
      (node (ref "R19") (pin "2") (pinfunction "2_2") (pintype "passive"))
    )
    (net (code "47") (name "Net-(P2-Pad3)") (class "Default")
      (node (ref "P2") (pin "3") (pinfunction "3_3") (pintype "passive"))
      (node (ref "R21") (pin "2") (pinfunction "2_2") (pintype "passive"))
    )
    (net (code "48") (name "Net-(P3-Pad2)") (class "Default")
      (node (ref "P3") (pin "2") (pinfunction "2_2") (pintype "passive"))
      (node (ref "R25") (pin "2") (pinfunction "2_2") (pintype "passive"))
    )
    (net (code "49") (name "Net-(P3-Pad3)") (class "Default")
      (node (ref "P3") (pin "3") (pinfunction "3_3") (pintype "passive"))
      (node (ref "R23") (pin "2") (pinfunction "2_2") (pintype "passive"))
    )
    (net (code "50") (name "Net-(R7-Pad2)") (class "Default")
      (node (ref "R7") (pin "2") (pinfunction "2_2") (pintype "passive"))
      (node (ref "SW2") (pin "1") (pinfunction "1_1") (pintype "passive"))
    )
    (net (code "51") (name "Net-(U1A-+)") (class "Default")
      (node (ref "R18") (pin "2") (pinfunction "2_2") (pintype "passive"))
      (node (ref "R19") (pin "1") (pinfunction "1_1") (pintype "passive"))
      (node (ref "U1") (pin "3") (pinfunction "+_3") (pintype "input"))
    )
    (net (code "52") (name "Net-(U1A--)") (class "Default")
      (node (ref "P2") (pin "1") (pinfunction "1_1") (pintype "passive"))
      (node (ref "U1") (pin "13") (pinfunction "-_13") (pintype "input"))
      (node (ref "U1") (pin "2") (pinfunction "-_2") (pintype "input"))
    )
    (net (code "53") (name "Net-(U1B-+)") (class "Default")
      (node (ref "R24") (pin "2") (pinfunction "2_2") (pintype "passive"))
      (node (ref "R25") (pin "1") (pinfunction "1_1") (pintype "passive"))
      (node (ref "U1") (pin "5") (pinfunction "+_5") (pintype "input"))
    )
    (net (code "54") (name "Net-(U1B--)") (class "Default")
      (node (ref "P3") (pin "1") (pinfunction "1_1") (pintype "passive"))
      (node (ref "U1") (pin "6") (pinfunction "-_6") (pintype "input"))
      (node (ref "U1") (pin "9") (pinfunction "-_9") (pintype "input"))
    )
    (net (code "55") (name "Net-(U1C-+)") (class "Default")
      (node (ref "R22") (pin "2") (pinfunction "2_2") (pintype "passive"))
      (node (ref "R23") (pin "1") (pinfunction "1_1") (pintype "passive"))
      (node (ref "U1") (pin "10") (pinfunction "+_10") (pintype "input"))
    )
    (net (code "56") (name "Net-(U1D-+)") (class "Default")
      (node (ref "R20") (pin "2") (pinfunction "2_2") (pintype "passive"))
      (node (ref "R21") (pin "1") (pinfunction "1_1") (pintype "passive"))
      (node (ref "U1") (pin "12") (pinfunction "+_12") (pintype "input"))
    )
    (net (code "57") (name "VDJ") (class "Default")
      (node (ref "C14") (pin "1") (pinfunction "1_1") (pintype "passive"))
      (node (ref "C15") (pin "1") (pinfunction "1_1") (pintype "passive"))
      (node (ref "C16") (pin "1") (pinfunction "1_1") (pintype "passive"))
      (node (ref "C17") (pin "1") (pinfunction "1_1") (pintype "passive"))
      (node (ref "C18") (pin "1") (pinfunction "1_1") (pintype "passive"))
      (node (ref "C19") (pin "1") (pinfunction "1_1") (pintype "passive"))
      (node (ref "C20") (pin "1") (pinfunction "1_1") (pintype "passive"))
      (node (ref "C21") (pin "1") (pinfunction "1_1") (pintype "passive"))
      (node (ref "C5") (pin "1") (pinfunction "1_1") (pintype "passive"))
      (node (ref "D1") (pin "1") (pinfunction "V+_1") (pintype "power_in"))
      (node (ref "D2") (pin "1") (pinfunction "V+_1") (pintype "power_in"))
      (node (ref "D3") (pin "1") (pinfunction "V+_1") (pintype "power_in"))
      (node (ref "D4") (pin "1") (pinfunction "V+_1") (pintype "power_in"))
      (node (ref "D5") (pin "1") (pinfunction "V+_1") (pintype "power_in"))
      (node (ref "D6") (pin "1") (pinfunction "V+_1") (pintype "power_in"))
      (node (ref "D7") (pin "1") (pinfunction "V+_1") (pintype "power_in"))
      (node (ref "D8") (pin "1") (pinfunction "V+_1") (pintype "power_in"))
      (node (ref "D9") (pin "C") (pinfunction "C_C") (pintype "passive"))
      (node (ref "T1") (pin "2") (pinfunction "S_2") (pintype "passive"))
      (node (ref "U2") (pin "1") (pinfunction "VIN_1") (pintype "power_in"))
      (node (ref "U2") (pin "3") (pinfunction "CE_3") (pintype "input"))
    )
    (net (code "58") (name "VSYS") (class "Default")
      (node (ref "P1") (pin "12") (pinfunction "12_12") (pintype "passive"))
      (node (ref "T1") (pin "3") (pinfunction "D_3") (pintype "passive"))
    )
    (net (code "59") (name "VUSB") (class "Default")
      (node (ref "D9") (pin "A") (pinfunction "A_A") (pintype "passive"))
      (node (ref "J1") (pin "A4") (pinfunction "VBUS_A4") (pintype "passive"))
      (node (ref "J1") (pin "A9") (pinfunction "VBUS_A9") (pintype "passive"))
      (node (ref "J1") (pin "B4") (pinfunction "VBUS_B4") (pintype "passive"))
      (node (ref "J1") (pin "B9") (pinfunction "VBUS_B9") (pintype "passive"))
      (node (ref "T1") (pin "1") (pinfunction "G_1") (pintype "passive"))
    )
    (net (code "60") (name "unconnected-(D8-Do-Pad2)") (class "Default")
      (node (ref "D8") (pin "2") (pinfunction "Do_2") (pintype "output"))
    )
    (net (code "61") (name "unconnected-(J1-SBU1-PadA8)") (class "Default")
      (node (ref "J1") (pin "A8") (pinfunction "SBU1_A8") (pintype "passive+no_connect"))
    )
    (net (code "62") (name "unconnected-(J1-SBU2-PadB8)") (class "Default")
      (node (ref "J1") (pin "B8") (pinfunction "SBU2_B8") (pintype "passive+no_connect"))
    )
    (net (code "63") (name "unconnected-(U2-N.C.-Pad4)") (class "Default")
      (node (ref "U2") (pin "4") (pinfunction "N.C._4") (pintype "passive+no_connect"))
    )
    (net (code "64") (name "unconnected-(U6-PB12-Pad23)") (class "Default")
      (node (ref "U6") (pin "23") (pinfunction "PB12_23") (pintype "bidirectional+no_connect"))
    )
  )
)
